# padControllerR3.net
KiCad netlist of a schematic drawn in EAGLE
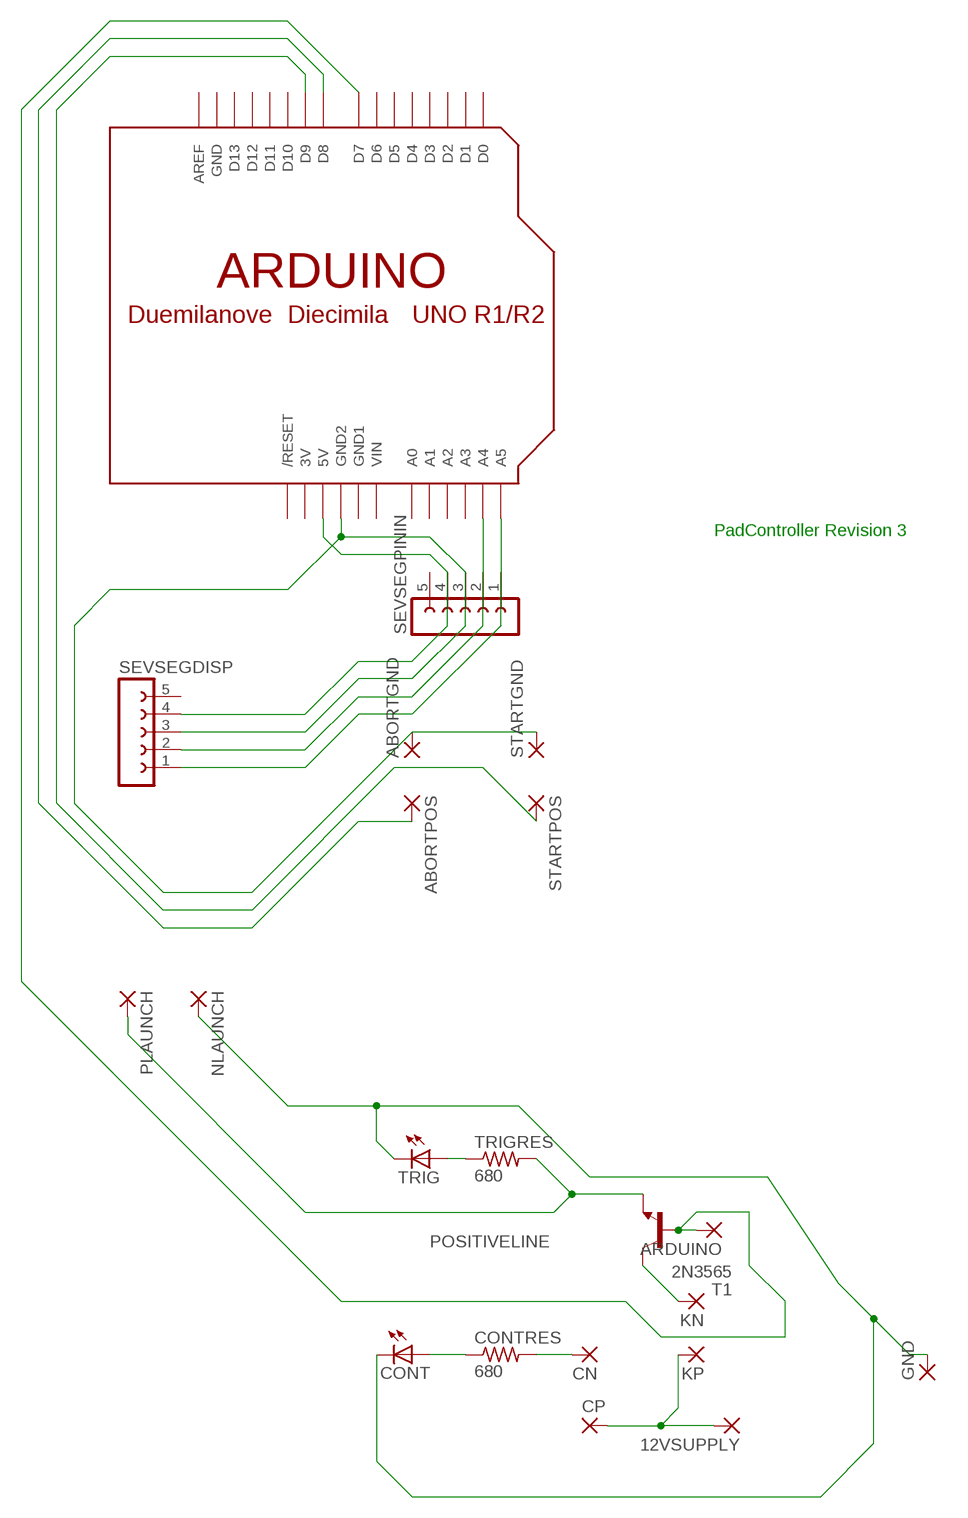
[diagram p0: schematic, sheet 1]

(export (version "E")
  (design (tool "Eeschema 10.0.6"))
  (components
    (comp (ref "12VSUPPLY")
      (value "3,17/1,1")
      (footprint "eagle-import:3,17_1,1")
      (libsource (lib "eagle-import") (part "3,17/1,1"))
    )
    (comp (ref "ABORTGND")
      (value "3,17/1,3")
      (footprint "eagle-import:3,17_1,3")
      (libsource (lib "eagle-import") (part "3,17/1,3"))
    )
    (comp (ref "ABORTPOS")
      (value "3,17/1,3")
      (footprint "eagle-import:3,17_1,3")
      (libsource (lib "eagle-import") (part "3,17/1,3"))
    )
    (comp (ref "ARDUINO")
      (value "3,17/1,3")
      (footprint "eagle-import:3,17_1,3")
      (libsource (lib "eagle-import") (part "3,17/1,3"))
    )
    (comp (ref "CN")
      (value "3,17/1,3")
      (footprint "eagle-import:3,17_1,3")
      (libsource (lib "eagle-import") (part "3,17/1,3"))
    )
    (comp (ref "CONT")
      (value "LED3MM")
      (footprint "eagle-import:LED3MM")
      (libsource (lib "eagle-import") (part "LED3MM"))
    )
    (comp (ref "CONTRES")
      (value "680")
      (footprint "eagle-import:0207_7")
      (libsource (lib "eagle-import") (part "R-US_0207/7"))
    )
    (comp (ref "CP")
      (value "3,17/1,3")
      (footprint "eagle-import:3,17_1,3")
      (libsource (lib "eagle-import") (part "3,17/1,3"))
    )
    (comp (ref "GND")
      (value "3,17/1,1")
      (footprint "eagle-import:3,17_1,1")
      (libsource (lib "eagle-import") (part "3,17/1,1"))
    )
    (comp (ref "KN")
      (value "3,17/1,3")
      (footprint "eagle-import:3,17_1,3")
      (libsource (lib "eagle-import") (part "3,17/1,3"))
    )
    (comp (ref "KP")
      (value "3,17/1,3")
      (footprint "eagle-import:3,17_1,3")
      (libsource (lib "eagle-import") (part "3,17/1,3"))
    )
    (comp (ref "NLAUNCH")
      (value "3,17/1,1")
      (footprint "eagle-import:3,17_1,1")
      (libsource (lib "eagle-import") (part "3,17/1,1"))
    )
    (comp (ref "PLAUNCH")
      (value "3,17/1,1")
      (footprint "eagle-import:3,17_1,1")
      (libsource (lib "eagle-import") (part "3,17/1,1"))
    )
    (comp (ref "SEVSEGDISP")
      (value "FE05-1")
      (footprint "eagle-import:FE05-1")
      (libsource (lib "eagle-import") (part "FE05-1"))
    )
    (comp (ref "SEVSEGPININ")
      (value "FE05-1")
      (footprint "eagle-import:FE05-1")
      (libsource (lib "eagle-import") (part "FE05-1"))
    )
    (comp (ref "STARTGND")
      (value "3,17/1,3")
      (footprint "eagle-import:3,17_1,3")
      (libsource (lib "eagle-import") (part "3,17/1,3"))
    )
    (comp (ref "STARTPOS")
      (value "3,17/1,3")
      (footprint "eagle-import:3,17_1,3")
      (libsource (lib "eagle-import") (part "3,17/1,3"))
    )
    (comp (ref "T1")
      (value "2N3565")
      (footprint "eagle-import:TO92")
      (libsource (lib "eagle-import") (part "2N3565"))
    )
    (comp (ref "TRIG")
      (value "LED3MM")
      (footprint "eagle-import:LED3MM")
      (libsource (lib "eagle-import") (part "LED3MM"))
    )
    (comp (ref "TRIGRES")
      (value "680")
      (footprint "eagle-import:0207_7")
      (libsource (lib "eagle-import") (part "R-US_0207/7"))
    )
    (comp (ref "U$1")
      (value "ARDUINO-NOHOLE")
      (footprint "eagle-import:ARDUINO-NOHOLE")
      (libsource (lib "eagle-import") (part "ARDUINO-NOHOLE"))
    )
  )
  (nets
    (net (code "1") (name "/3V") (class "Default")
      (node (ref "U$1") (pin "3V") (pinfunction "3V_3V") (pintype "power_in"))
    )
    (net (code "2") (name "/GND") (class "Default")
      (node (ref "U$1") (pin "GND") (pinfunction "GND_GND") (pintype "power_in"))
    )
    (net (code "3") (name "/GND1") (class "Default")
      (node (ref "U$1") (pin "GND1") (pinfunction "GND1_GND1") (pintype "power_in"))
    )
    (net (code "4") (name "/POSITIVELINE") (class "Default")
      (node (ref "PLAUNCH") (pin "1") (pinfunction "P_1") (pintype "passive"))
      (node (ref "T1") (pin "3") (pinfunction "E_3") (pintype "passive"))
      (node (ref "TRIGRES") (pin "2") (pinfunction "2_2") (pintype "passive"))
    )
    (net (code "5") (name "/VIN") (class "Default")
      (node (ref "U$1") (pin "VIN") (pinfunction "VIN_VIN") (pintype "power_in"))
    )
    (net (code "6") (name "Net-(12VSUPPLY-P)") (class "Default")
      (node (ref "12VSUPPLY") (pin "1") (pinfunction "P_1") (pintype "passive"))
      (node (ref "CP") (pin "1") (pinfunction "P_1") (pintype "passive"))
      (node (ref "KP") (pin "1") (pinfunction "P_1") (pintype "passive"))
    )
    (net (code "7") (name "Net-(ABORTGND-P)") (class "Default")
      (node (ref "ABORTGND") (pin "1") (pinfunction "P_1") (pintype "passive"))
      (node (ref "SEVSEGDISP") (pin "3") (pinfunction "3_3") (pintype "passive"))
      (node (ref "SEVSEGPININ") (pin "3") (pinfunction "3_3") (pintype "passive"))
      (node (ref "STARTGND") (pin "1") (pinfunction "P_1") (pintype "passive"))
      (node (ref "U$1") (pin "GND2") (pinfunction "GND2_GND2") (pintype "power_in"))
    )
    (net (code "8") (name "Net-(ABORTPOS-P)") (class "Default")
      (node (ref "ABORTPOS") (pin "1") (pinfunction "P_1") (pintype "passive"))
      (node (ref "U$1") (pin "D8") (pinfunction "D8_D8") (pintype "bidirectional"))
    )
    (net (code "9") (name "Net-(ARDUINO-P)") (class "Default")
      (node (ref "ARDUINO") (pin "1") (pinfunction "P_1") (pintype "passive"))
      (node (ref "T1") (pin "2") (pinfunction "B_2") (pintype "passive"))
      (node (ref "U$1") (pin "D7") (pinfunction "D7_D7") (pintype "bidirectional"))
    )
    (net (code "10") (name "Net-(CN-P)") (class "Default")
      (node (ref "CN") (pin "1") (pinfunction "P_1") (pintype "passive"))
      (node (ref "CONTRES") (pin "2") (pinfunction "2_2") (pintype "passive"))
    )
    (net (code "11") (name "Net-(CONT-C)") (class "Default")
      (node (ref "CONT") (pin "K") (pinfunction "C_K") (pintype "passive"))
      (node (ref "GND") (pin "1") (pinfunction "P_1") (pintype "passive"))
      (node (ref "NLAUNCH") (pin "1") (pinfunction "P_1") (pintype "passive"))
      (node (ref "TRIG") (pin "K") (pinfunction "C_K") (pintype "passive"))
    )
    (net (code "12") (name "Net-(CONT-PadA)") (class "Default")
      (node (ref "CONT") (pin "A") (pinfunction "A_A") (pintype "passive"))
      (node (ref "CONTRES") (pin "1") (pinfunction "1_1") (pintype "passive"))
    )
    (net (code "13") (name "Net-(KN-P)") (class "Default")
      (node (ref "KN") (pin "1") (pinfunction "P_1") (pintype "passive"))
      (node (ref "T1") (pin "1") (pinfunction "C_1") (pintype "passive"))
    )
    (net (code "14") (name "Net-(SEVSEGDISP-Pad1)") (class "Default")
      (node (ref "SEVSEGDISP") (pin "1") (pinfunction "1_1") (pintype "passive"))
      (node (ref "SEVSEGPININ") (pin "1") (pinfunction "1_1") (pintype "passive"))
      (node (ref "U$1") (pin "A5") (pinfunction "A5_A5") (pintype "bidirectional"))
    )
    (net (code "15") (name "Net-(SEVSEGDISP-Pad2)") (class "Default")
      (node (ref "SEVSEGDISP") (pin "2") (pinfunction "2_2") (pintype "passive"))
      (node (ref "SEVSEGPININ") (pin "2") (pinfunction "2_2") (pintype "passive"))
      (node (ref "U$1") (pin "A4") (pinfunction "A4_A4") (pintype "bidirectional"))
    )
    (net (code "16") (name "Net-(SEVSEGDISP-Pad4)") (class "Default")
      (node (ref "SEVSEGDISP") (pin "4") (pinfunction "4_4") (pintype "passive"))
      (node (ref "SEVSEGPININ") (pin "4") (pinfunction "4_4") (pintype "passive"))
      (node (ref "U$1") (pin "5V") (pinfunction "5V_5V") (pintype "power_in"))
    )
    (net (code "17") (name "Net-(STARTPOS-P)") (class "Default")
      (node (ref "STARTPOS") (pin "1") (pinfunction "P_1") (pintype "passive"))
      (node (ref "U$1") (pin "D9") (pinfunction "D9_D9") (pintype "bidirectional"))
    )
    (net (code "18") (name "Net-(TRIG-PadA)") (class "Default")
      (node (ref "TRIG") (pin "A") (pinfunction "A_A") (pintype "passive"))
      (node (ref "TRIGRES") (pin "1") (pinfunction "1_1") (pintype "passive"))
    )
    (net (code "19") (name "unconnected-(SEVSEGDISP-Pad5)") (class "Default")
      (node (ref "SEVSEGDISP") (pin "5") (pinfunction "5_5") (pintype "passive"))
    )
    (net (code "20") (name "unconnected-(SEVSEGPININ-Pad5)") (class "Default")
      (node (ref "SEVSEGPININ") (pin "5") (pinfunction "5_5") (pintype "passive"))
    )
    (net (code "21") (name "unconnected-(U$1-PadA0)") (class "Default")
      (node (ref "U$1") (pin "A0") (pinfunction "A0_A0") (pintype "bidirectional"))
    )
    (net (code "22") (name "unconnected-(U$1-PadA1)") (class "Default")
      (node (ref "U$1") (pin "A1") (pinfunction "A1_A1") (pintype "bidirectional"))
    )
    (net (code "23") (name "unconnected-(U$1-PadA2)") (class "Default")
      (node (ref "U$1") (pin "A2") (pinfunction "A2_A2") (pintype "bidirectional"))
    )
    (net (code "24") (name "unconnected-(U$1-PadA3)") (class "Default")
      (node (ref "U$1") (pin "A3") (pinfunction "A3_A3") (pintype "bidirectional"))
    )
    (net (code "25") (name "unconnected-(U$1-PadAREF)") (class "Default")
      (node (ref "U$1") (pin "AREF") (pinfunction "AREF_AREF") (pintype "bidirectional"))
    )
    (net (code "26") (name "unconnected-(U$1-PadD0)") (class "Default")
      (node (ref "U$1") (pin "D0") (pinfunction "D0_D0") (pintype "bidirectional"))
    )
    (net (code "27") (name "unconnected-(U$1-PadD1)") (class "Default")
      (node (ref "U$1") (pin "D1") (pinfunction "D1_D1") (pintype "bidirectional"))
    )
    (net (code "28") (name "unconnected-(U$1-PadD2)") (class "Default")
      (node (ref "U$1") (pin "D2") (pinfunction "D2_D2") (pintype "bidirectional"))
    )
    (net (code "29") (name "unconnected-(U$1-PadD3)") (class "Default")
      (node (ref "U$1") (pin "D3") (pinfunction "D3_D3") (pintype "bidirectional"))
    )
    (net (code "30") (name "unconnected-(U$1-PadD4)") (class "Default")
      (node (ref "U$1") (pin "D4") (pinfunction "D4_D4") (pintype "bidirectional"))
    )
    (net (code "31") (name "unconnected-(U$1-PadD5)") (class "Default")
      (node (ref "U$1") (pin "D5") (pinfunction "D5_D5") (pintype "bidirectional"))
    )
    (net (code "32") (name "unconnected-(U$1-PadD6)") (class "Default")
      (node (ref "U$1") (pin "D6") (pinfunction "D6_D6") (pintype "bidirectional"))
    )
    (net (code "33") (name "unconnected-(U$1-PadD10)") (class "Default")
      (node (ref "U$1") (pin "D10") (pinfunction "D10_D10") (pintype "bidirectional"))
    )
    (net (code "34") (name "unconnected-(U$1-PadD11)") (class "Default")
      (node (ref "U$1") (pin "D11") (pinfunction "D11_D11") (pintype "bidirectional"))
    )
    (net (code "35") (name "unconnected-(U$1-PadD12)") (class "Default")
      (node (ref "U$1") (pin "D12") (pinfunction "D12_D12") (pintype "bidirectional"))
    )
    (net (code "36") (name "unconnected-(U$1-PadD13)") (class "Default")
      (node (ref "U$1") (pin "D13") (pinfunction "D13_D13") (pintype "bidirectional"))
    )
    (net (code "37") (name "unconnected-(U$1-{slash}RESET-PadRESET)") (class "Default")
      (node (ref "U$1") (pin "RESET") (pinfunction "/RESET_RESET") (pintype "bidirectional"))
    )
  )
)
